# Simple-Bug-2SC9014.net
KiCad netlist of a schematic drawn in EAGLE
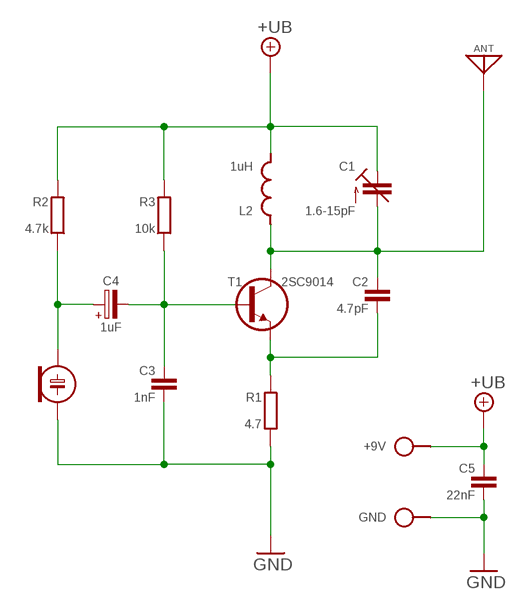
[diagram p0: schematic, sheet 1]

(export (version "E")
  (design (tool "Eeschema 10.0.6"))
  (components
    (comp (ref "+9V")
      (value "SPAD")
      (footprint "eagle-import:SPAD")
      (libsource (lib "eagle-import") (part "SPAD"))
    )
    (comp (ref "ANT")
      (value "ANT")
      (footprint "eagle-import:SPAD")
      (libsource (lib "eagle-import") (part "ANT"))
    )
    (comp (ref "C1")
      (value "1.6-15pF")
      (footprint "eagle-import:TRIM-2222-808")
      (libsource (lib "eagle-import") (part "C-TR-PH20127"))
    )
    (comp (ref "C2")
      (value "4.7pF")
      (footprint "eagle-import:C050-020X036")
      (libsource (lib "eagle-import") (part "C050-020X036"))
    )
    (comp (ref "C3")
      (value "1nF")
      (footprint "eagle-import:C050-020X036_V")
      (libsource (lib "eagle-import") (part "C050-020X036/V"))
    )
    (comp (ref "C4")
      (value "1uF")
      (footprint "eagle-import:E2,5-3_V")
      (libsource (lib "eagle-import") (part "CPOLE2,5-3/V"))
    )
    (comp (ref "C5")
      (value "22nF")
      (footprint "eagle-import:C050-020X036_V")
      (libsource (lib "eagle-import") (part "C050-020X036/V"))
    )
    (comp (ref "ECM")
      (value "ECM-4")
      (footprint "eagle-import:ECM-4")
      (libsource (lib "eagle-import") (part "ECM-4"))
    )
    (comp (ref "GND")
      (value "SPAD")
      (footprint "eagle-import:SPAD")
      (libsource (lib "eagle-import") (part "SPAD"))
    )
    (comp (ref "L2")
      (value "1uH")
      (footprint "eagle-import:L-04_7V")
      (libsource (lib "eagle-import") (part "L-SHORTL-04/7V"))
    )
    (comp (ref "R1")
      (value "4.7")
      (footprint "eagle-import:0204_2V")
      (libsource (lib "eagle-import") (part "R0204/2V"))
    )
    (comp (ref "R2")
      (value "4.7k")
      (footprint "eagle-import:0204_7-V")
      (libsource (lib "eagle-import") (part "R0204/7-V"))
    )
    (comp (ref "R3")
      (value "10k")
      (footprint "eagle-import:0204_7-V")
      (libsource (lib "eagle-import") (part "R0204/7-V"))
    )
    (comp (ref "T1")
      (value "2SC9014")
      (footprint "eagle-import:TO92-EBC")
      (libsource (lib "eagle-import") (part "2SC9014"))
    )
  )
  (nets
    (net (code "1") (name "+UB") (class "Default")
      (node (ref "+9V") (pin "1") (pinfunction "P$1_1") (pintype "bidirectional"))
      (node (ref "C1") (pin "1") (pinfunction "E_1") (pintype "passive"))
      (node (ref "C1") (pin "3") (pinfunction "E_3") (pintype "passive"))
      (node (ref "C5") (pin "1") (pinfunction "1_1") (pintype "passive"))
      (node (ref "L2") (pin "2") (pinfunction "2_2") (pintype "passive"))
      (node (ref "R2") (pin "1") (pinfunction "1_1") (pintype "passive"))
      (node (ref "R3") (pin "1") (pinfunction "1_1") (pintype "passive"))
    )
    (net (code "2") (name "GND") (class "Default")
      (node (ref "C3") (pin "2") (pinfunction "2_2") (pintype "passive"))
      (node (ref "C5") (pin "2") (pinfunction "2_2") (pintype "passive"))
      (node (ref "ECM") (pin "2") (pinfunction "-_2") (pintype "passive"))
      (node (ref "GND") (pin "1") (pinfunction "P$1_1") (pintype "bidirectional"))
      (node (ref "R1") (pin "2") (pinfunction "2_2") (pintype "passive"))
    )
    (net (code "3") (name "Net-(C1-A)") (class "Default")
      (node (ref "ANT") (pin "1") (pinfunction "1_1") (pintype "output"))
      (node (ref "C1") (pin "2") (pinfunction "A_2") (pintype "passive"))
      (node (ref "C2") (pin "1") (pinfunction "1_1") (pintype "passive"))
      (node (ref "L2") (pin "1") (pinfunction "1_1") (pintype "passive"))
      (node (ref "T1") (pin "C") (pinfunction "C_C") (pintype "passive"))
    )
    (net (code "4") (name "Net-(C2-Pad2)") (class "Default")
      (node (ref "C2") (pin "2") (pinfunction "2_2") (pintype "passive"))
      (node (ref "R1") (pin "1") (pinfunction "1_1") (pintype "passive"))
      (node (ref "T1") (pin "E") (pinfunction "E_E") (pintype "passive"))
    )
    (net (code "5") (name "Net-(C3-Pad1)") (class "Default")
      (node (ref "C3") (pin "1") (pinfunction "1_1") (pintype "passive"))
      (node (ref "C4") (pin "-") (pinfunction "-_-") (pintype "passive"))
      (node (ref "R3") (pin "2") (pinfunction "2_2") (pintype "passive"))
      (node (ref "T1") (pin "B") (pinfunction "B_B") (pintype "passive"))
    )
    (net (code "6") (name "Net-(ECM-+)") (class "Default")
      (node (ref "C4") (pin "+") (pinfunction "+_+") (pintype "passive"))
      (node (ref "ECM") (pin "1") (pinfunction "+_1") (pintype "passive"))
      (node (ref "R2") (pin "2") (pinfunction "2_2") (pintype "passive"))
    )
  )
)
